# m1k-buffermod-s2.net
KiCad netlist of a schematic drawn in EAGLE
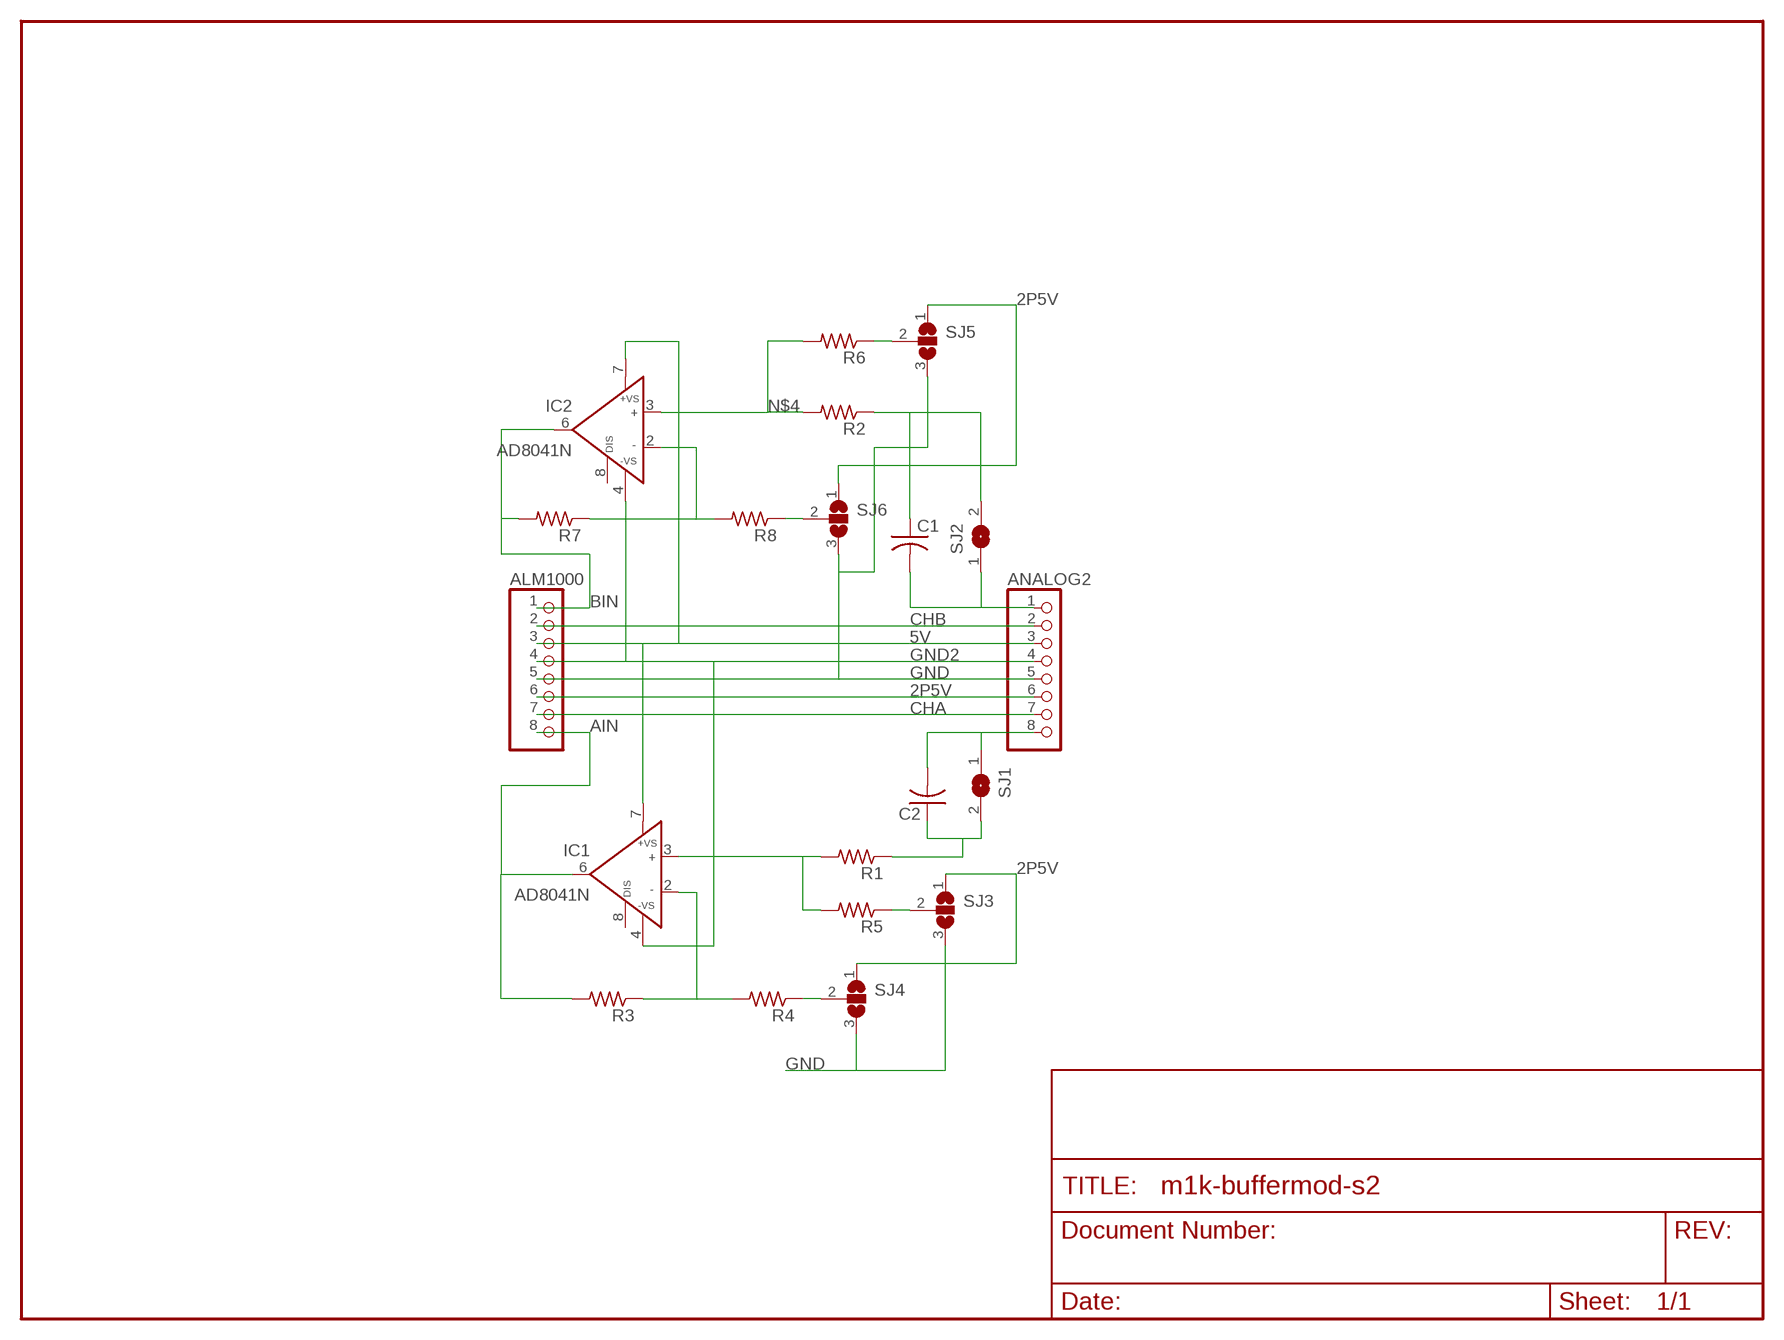
[diagram p0: schematic, sheet 1]

(export (version "E")
  (design (tool "Eeschema 10.0.6"))
  (components
    (comp (ref "ALM1000")
      (value "PINHD-1X8")
      (footprint "eagle-import:1X08")
      (libsource (lib "eagle-import") (part "PINHD-1X8"))
    )
    (comp (ref "ANALOG2")
      (value "PINHD-1X8")
      (footprint "eagle-import:1X08")
      (libsource (lib "eagle-import") (part "PINHD-1X8"))
    )
    (comp (ref "C1")
      (value "C-US050-024X044")
      (footprint "eagle-import:C050-024X044")
      (libsource (lib "eagle-import") (part "C-US050-024X044"))
    )
    (comp (ref "C2")
      (value "C-US050-024X044")
      (footprint "eagle-import:C050-024X044")
      (libsource (lib "eagle-import") (part "C-US050-024X044"))
    )
    (comp (ref "IC1")
      (value "AD8041N")
      (footprint "eagle-import:DIL08")
      (fields (field (name "MPN") "AD8041ANZ"))
      (libsource (lib "eagle-import") (part "AD8041N"))
    )
    (comp (ref "IC2")
      (value "AD8041N")
      (footprint "eagle-import:DIL08")
      (fields (field (name "MPN") "AD8041ANZ"))
      (libsource (lib "eagle-import") (part "AD8041N"))
    )
    (comp (ref "R1")
      (value "R-US_0204/7")
      (footprint "eagle-import:0204_7")
      (libsource (lib "eagle-import") (part "R-US_0204/7"))
    )
    (comp (ref "R2")
      (value "R-US_0204/7")
      (footprint "eagle-import:0204_7")
      (libsource (lib "eagle-import") (part "R-US_0204/7"))
    )
    (comp (ref "R3")
      (value "R-US_0204/7")
      (footprint "eagle-import:0204_7")
      (libsource (lib "eagle-import") (part "R-US_0204/7"))
    )
    (comp (ref "R4")
      (value "R-US_0204/7")
      (footprint "eagle-import:0204_7")
      (libsource (lib "eagle-import") (part "R-US_0204/7"))
    )
    (comp (ref "R5")
      (value "R-US_0204/7")
      (footprint "eagle-import:0204_7")
      (libsource (lib "eagle-import") (part "R-US_0204/7"))
    )
    (comp (ref "R6")
      (value "R-US_0204/7")
      (footprint "eagle-import:0204_7")
      (libsource (lib "eagle-import") (part "R-US_0204/7"))
    )
    (comp (ref "R7")
      (value "R-US_0204/7")
      (footprint "eagle-import:0204_7")
      (libsource (lib "eagle-import") (part "R-US_0204/7"))
    )
    (comp (ref "R8")
      (value "R-US_0204/7")
      (footprint "eagle-import:0204_7")
      (libsource (lib "eagle-import") (part "R-US_0204/7"))
    )
    (comp (ref "SJ1") (value "SJ") (footprint "eagle-import:SJ") (libsource (lib "eagle-import") (part "SJ")))
    (comp (ref "SJ2") (value "SJ") (footprint "eagle-import:SJ") (libsource (lib "eagle-import") (part "SJ")))
    (comp (ref "SJ3")
      (value "SJ2W")
      (footprint "eagle-import:SJ_2")
      (libsource (lib "eagle-import") (part "SJ2W"))
    )
    (comp (ref "SJ4")
      (value "SJ2W")
      (footprint "eagle-import:SJ_2")
      (libsource (lib "eagle-import") (part "SJ2W"))
    )
    (comp (ref "SJ5")
      (value "SJ2W")
      (footprint "eagle-import:SJ_2")
      (libsource (lib "eagle-import") (part "SJ2W"))
    )
    (comp (ref "SJ6")
      (value "SJ2W")
      (footprint "eagle-import:SJ_2")
      (libsource (lib "eagle-import") (part "SJ2W"))
    )
  )
  (nets
    (net (code "1") (name "/2P5V") (class "Default")
      (node (ref "ALM1000") (pin "6") (pinfunction "6_6") (pintype "passive"))
      (node (ref "ANALOG2") (pin "6") (pinfunction "6_6") (pintype "passive"))
      (node (ref "SJ3") (pin "1") (pinfunction "1_1") (pintype "passive"))
      (node (ref "SJ4") (pin "1") (pinfunction "1_1") (pintype "passive"))
      (node (ref "SJ5") (pin "1") (pinfunction "1_1") (pintype "passive"))
      (node (ref "SJ6") (pin "1") (pinfunction "1_1") (pintype "passive"))
    )
    (net (code "2") (name "/5V") (class "Default")
      (node (ref "ALM1000") (pin "3") (pinfunction "3_3") (pintype "passive"))
      (node (ref "ANALOG2") (pin "3") (pinfunction "3_3") (pintype "passive"))
      (node (ref "IC1") (pin "7") (pinfunction "+VS_7") (pintype "input"))
      (node (ref "IC2") (pin "7") (pinfunction "+VS_7") (pintype "input"))
    )
    (net (code "3") (name "/AIN") (class "Default")
      (node (ref "ALM1000") (pin "8") (pinfunction "8_8") (pintype "passive"))
      (node (ref "IC1") (pin "6") (pinfunction "OUT_6") (pintype "output"))
      (node (ref "R3") (pin "2") (pinfunction "2_2") (pintype "passive"))
    )
    (net (code "4") (name "/BIN") (class "Default")
      (node (ref "ALM1000") (pin "1") (pinfunction "1_1") (pintype "passive"))
      (node (ref "IC2") (pin "6") (pinfunction "OUT_6") (pintype "output"))
      (node (ref "R7") (pin "2") (pinfunction "2_2") (pintype "passive"))
    )
    (net (code "5") (name "/CHA") (class "Default")
      (node (ref "ALM1000") (pin "7") (pinfunction "7_7") (pintype "passive"))
      (node (ref "ANALOG2") (pin "7") (pinfunction "7_7") (pintype "passive"))
    )
    (net (code "6") (name "/CHB") (class "Default")
      (node (ref "ALM1000") (pin "2") (pinfunction "2_2") (pintype "passive"))
      (node (ref "ANALOG2") (pin "2") (pinfunction "2_2") (pintype "passive"))
    )
    (net (code "7") (name "/GND") (class "Default")
      (node (ref "ALM1000") (pin "5") (pinfunction "5_5") (pintype "passive"))
      (node (ref "ANALOG2") (pin "5") (pinfunction "5_5") (pintype "passive"))
      (node (ref "SJ3") (pin "3") (pinfunction "3_3") (pintype "passive"))
      (node (ref "SJ4") (pin "3") (pinfunction "3_3") (pintype "passive"))
      (node (ref "SJ5") (pin "3") (pinfunction "3_3") (pintype "passive"))
      (node (ref "SJ6") (pin "3") (pinfunction "3_3") (pintype "passive"))
    )
    (net (code "8") (name "/GND2") (class "Default")
      (node (ref "ALM1000") (pin "4") (pinfunction "4_4") (pintype "passive"))
      (node (ref "ANALOG2") (pin "4") (pinfunction "4_4") (pintype "passive"))
      (node (ref "IC1") (pin "4") (pinfunction "-VS_4") (pintype "input"))
      (node (ref "IC2") (pin "4") (pinfunction "-VS_4") (pintype "input"))
    )
    (net (code "9") (name "/N$4") (class "Default")
      (node (ref "IC2") (pin "3") (pinfunction "IN+_3") (pintype "input"))
      (node (ref "R2") (pin "2") (pinfunction "2_2") (pintype "passive"))
      (node (ref "R6") (pin "2") (pinfunction "2_2") (pintype "passive"))
    )
    (net (code "10") (name "Net-(ANALOG2-Pad1)") (class "Default")
      (node (ref "ANALOG2") (pin "1") (pinfunction "1_1") (pintype "passive"))
      (node (ref "C1") (pin "2") (pinfunction "2_2") (pintype "passive"))
      (node (ref "SJ2") (pin "1") (pinfunction "1_1") (pintype "passive"))
    )
    (net (code "11") (name "Net-(ANALOG2-Pad8)") (class "Default")
      (node (ref "ANALOG2") (pin "8") (pinfunction "8_8") (pintype "passive"))
      (node (ref "C2") (pin "2") (pinfunction "2_2") (pintype "passive"))
      (node (ref "SJ1") (pin "1") (pinfunction "1_1") (pintype "passive"))
    )
    (net (code "12") (name "Net-(C1-Pad1)") (class "Default")
      (node (ref "C1") (pin "1") (pinfunction "1_1") (pintype "passive"))
      (node (ref "R2") (pin "1") (pinfunction "1_1") (pintype "passive"))
      (node (ref "SJ2") (pin "2") (pinfunction "2_2") (pintype "passive"))
    )
    (net (code "13") (name "Net-(C2-Pad1)") (class "Default")
      (node (ref "C2") (pin "1") (pinfunction "1_1") (pintype "passive"))
      (node (ref "R1") (pin "1") (pinfunction "1_1") (pintype "passive"))
      (node (ref "SJ1") (pin "2") (pinfunction "2_2") (pintype "passive"))
    )
    (net (code "14") (name "Net-(IC1-IN+)") (class "Default")
      (node (ref "IC1") (pin "3") (pinfunction "IN+_3") (pintype "input"))
      (node (ref "R1") (pin "2") (pinfunction "2_2") (pintype "passive"))
      (node (ref "R5") (pin "2") (pinfunction "2_2") (pintype "passive"))
    )
    (net (code "15") (name "Net-(IC1-IN-)") (class "Default")
      (node (ref "IC1") (pin "2") (pinfunction "IN-_2") (pintype "input"))
      (node (ref "R3") (pin "1") (pinfunction "1_1") (pintype "passive"))
      (node (ref "R4") (pin "2") (pinfunction "2_2") (pintype "passive"))
    )
    (net (code "16") (name "Net-(IC2-IN-)") (class "Default")
      (node (ref "IC2") (pin "2") (pinfunction "IN-_2") (pintype "input"))
      (node (ref "R7") (pin "1") (pinfunction "1_1") (pintype "passive"))
      (node (ref "R8") (pin "2") (pinfunction "2_2") (pintype "passive"))
    )
    (net (code "17") (name "Net-(R4-Pad1)") (class "Default")
      (node (ref "R4") (pin "1") (pinfunction "1_1") (pintype "passive"))
      (node (ref "SJ4") (pin "2") (pinfunction "2_2") (pintype "passive"))
    )
    (net (code "18") (name "Net-(R5-Pad1)") (class "Default")
      (node (ref "R5") (pin "1") (pinfunction "1_1") (pintype "passive"))
      (node (ref "SJ3") (pin "2") (pinfunction "2_2") (pintype "passive"))
    )
    (net (code "19") (name "Net-(R6-Pad1)") (class "Default")
      (node (ref "R6") (pin "1") (pinfunction "1_1") (pintype "passive"))
      (node (ref "SJ5") (pin "2") (pinfunction "2_2") (pintype "passive"))
    )
    (net (code "20") (name "Net-(R8-Pad1)") (class "Default")
      (node (ref "R8") (pin "1") (pinfunction "1_1") (pintype "passive"))
      (node (ref "SJ6") (pin "2") (pinfunction "2_2") (pintype "passive"))
    )
    (net (code "21") (name "unconnected-(IC1-DISABLE-Pad8)") (class "Default")
      (node (ref "IC1") (pin "8") (pinfunction "DISABLE_8") (pintype "passive"))
    )
    (net (code "22") (name "unconnected-(IC2-DISABLE-Pad8)") (class "Default")
      (node (ref "IC2") (pin "8") (pinfunction "DISABLE_8") (pintype "passive"))
    )
  )
)
